# 02-USER_IO_STATUS.net
KiCad netlist of a schematic drawn in Altium Designer
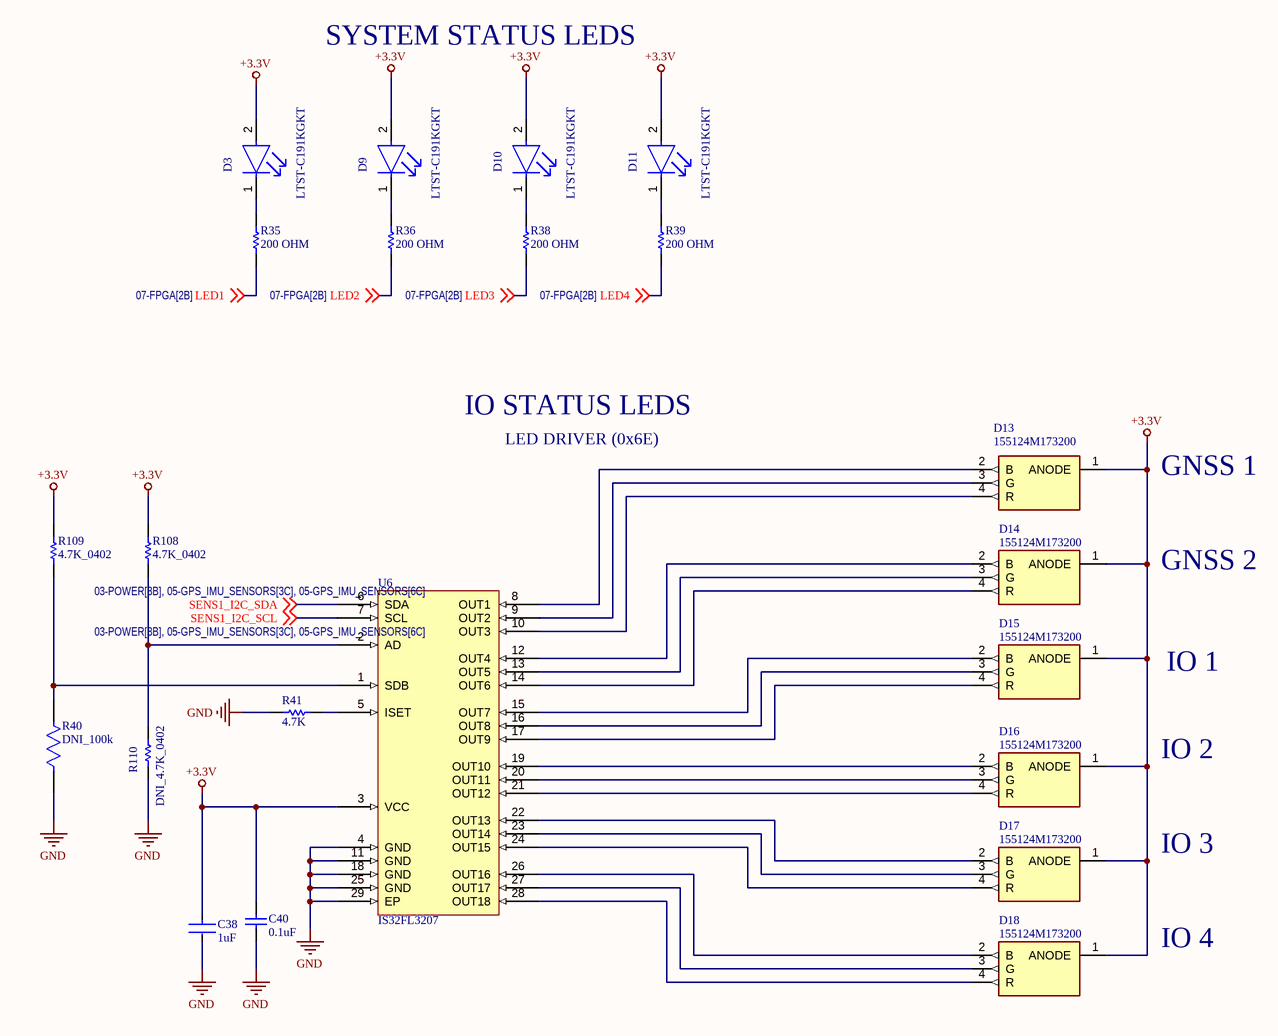
[diagram p0: 02-USER_IO_STATUS.SchDoc]

(export (version "E")
  (design (tool "Eeschema 10.0.6"))
  (components
    (comp (ref "C38")
      (value "1uF")
      (footprint "FP-C0603C105K3PACTU-MFG")
      (description "CAP CER 1UF 25V X5R 0603")
      (fields (field (name "VOLTAGE") "25V") (field (name "TOLERANCE") "10%"))
      (libsource (lib "Altium Content Vault") (part "e9c51b7dd13d4faca003ae77663ab08"))
    )
    (comp (ref "C40")
      (value "0.1uF")
      (footprint "CAPC1608X87X45ML20T05")
      (description "C0603X104K5RACAUTO")
      (fields (field (name "MANUFACTURER") "Kemet"))
      (libsource (lib "Altium Content Vault") (part "CAP"))
    )
    (comp (ref "D3")
      (value "LTST-C191KGKT")
      (footprint "FP-LTST-C191KGKT-MFG")
      (description "LED GREEN CLEAR SMD")
      (libsource (lib "Altium Content Vault") (part "8706943c75ba83719d021d2fdc84c58"))
    )
    (comp (ref "D9")
      (value "LTST-C191KGKT")
      (footprint "FP-LTST-C191KGKT-MFG")
      (description "LED GREEN CLEAR SMD")
      (libsource (lib "Altium Content Vault") (part "8706943c75ba83719d021d2fdc84c58"))
    )
    (comp (ref "D10")
      (value "LTST-C191KGKT")
      (footprint "FP-LTST-C191KGKT-MFG")
      (description "LED GREEN CLEAR SMD")
      (libsource (lib "Altium Content Vault") (part "8706943c75ba83719d021d2fdc84c58"))
    )
    (comp (ref "D11")
      (value "LTST-C191KGKT")
      (footprint "FP-LTST-C191KGKT-MFG")
      (description "LED GREEN CLEAR SMD")
      (libsource (lib "Altium Content Vault") (part "8706943c75ba83719d021d2fdc84c58"))
    )
    (comp (ref "D13")
      (value "155124M173200")
      (footprint "SamacSys:155124M173200")
      (description "LED (Multiple)")
      (fields (field (name "MOUSER PART NUMBER") "710-155124M173200"))
      (libsource (lib "SamacSys") (part "155124M173200"))
    )
    (comp (ref "D14")
      (value "155124M173200")
      (footprint "SamacSys:155124M173200")
      (description "LED (Multiple)")
      (fields (field (name "MOUSER PART NUMBER") "710-155124M173200"))
      (libsource (lib "SamacSys") (part "155124M173200"))
    )
    (comp (ref "D15")
      (value "155124M173200")
      (footprint "SamacSys:155124M173200")
      (description "LED (Multiple)")
      (fields (field (name "MOUSER PART NUMBER") "710-155124M173200"))
      (libsource (lib "SamacSys") (part "155124M173200"))
    )
    (comp (ref "D16")
      (value "155124M173200")
      (footprint "SamacSys:155124M173200")
      (description "LED (Multiple)")
      (fields (field (name "MOUSER PART NUMBER") "710-155124M173200"))
      (libsource (lib "SamacSys") (part "155124M173200"))
    )
    (comp (ref "D17")
      (value "155124M173200")
      (footprint "SamacSys:155124M173200")
      (description "LED (Multiple)")
      (fields (field (name "MOUSER PART NUMBER") "710-155124M173200"))
      (libsource (lib "SamacSys") (part "155124M173200"))
    )
    (comp (ref "D18")
      (value "155124M173200")
      (footprint "SamacSys:155124M173200")
      (description "LED (Multiple)")
      (fields (field (name "MOUSER PART NUMBER") "710-155124M173200"))
      (libsource (lib "SamacSys") (part "155124M173200"))
    )
    (comp (ref "R35")
      (value "200 OHM")
      (footprint "RESC1608X55X30NL15T15")
      (description "ERJ-3EKF2000V")
      (fields (field (name "MANUFACTURER") "Panasonic"))
      (libsource (lib "Altium Content Vault") (part "RES"))
    )
    (comp (ref "R36")
      (value "200 OHM")
      (footprint "RESC1608X55X30NL15T15")
      (description "ERJ-3EKF2000V")
      (fields (field (name "MANUFACTURER") "Panasonic"))
      (libsource (lib "Altium Content Vault") (part "RES"))
    )
    (comp (ref "R38")
      (value "200 OHM")
      (footprint "RESC1608X55X30NL15T15")
      (description "ERJ-3EKF2000V")
      (fields (field (name "MANUFACTURER") "Panasonic"))
      (libsource (lib "Altium Content Vault") (part "RES"))
    )
    (comp (ref "R39")
      (value "200 OHM")
      (footprint "RESC1608X55X30NL15T15")
      (description "ERJ-3EKF2000V")
      (fields (field (name "MANUFACTURER") "Panasonic"))
      (libsource (lib "Altium Content Vault") (part "RES"))
    )
    (comp (ref "R40")
      (value "DNI_100k")
      (footprint "FP-RC0603-0_55-MFG")
      (description "RES SMD 100K OHM 1% 1/10W 0603")
      (fields (field (name "TOLERANCE") "1%"))
      (libsource (lib "Altium Content Vault") (part "1029c3af85768c4190bb7ad29bc67b5"))
    )
    (comp (ref "R41")
      (value "4.7K")
      (footprint "RESC1608X55X30NL15T15")
      (fields (field (name "TOLERANCE") "5%"))
      (libsource (lib "Altium Content Vault") (part "RES-2"))
    )
    (comp (ref "R108")
      (value "4.7K_0402")
      (footprint "RESC1005X40X25LL05T05")
      (description "Chip Resistor, 4.7 KOhm, +/- 1%, 0.1 W, -55 to 155 degC, 0402 (1005 Metric), RoHS, Tape and Reel")
      (fields (field (name "TOLERANCE") "1%") (field (name "PARTNUMBER") "ERJ-2RKF4701X"))
      (libsource (lib "Altium Content Vault") (part "RES-2"))
    )
    (comp (ref "R109")
      (value "4.7K_0402")
      (footprint "RESC1005X40X25LL05T05")
      (description "Chip Resistor, 4.7 KOhm, +/- 1%, 0.1 W, -55 to 155 degC, 0402 (1005 Metric), RoHS, Tape and Reel")
      (fields (field (name "TOLERANCE") "1%") (field (name "PARTNUMBER") "ERJ-2RKF4701X"))
      (libsource (lib "Altium Content Vault") (part "RES-2"))
    )
    (comp (ref "R110")
      (value "DNI_4.7K_0402")
      (footprint "RESC1005X40X25LL05T05")
      (description "Chip Resistor, 4.7 KOhm, +/- 1%, 0.1 W, -55 to 155 degC, 0402 (1005 Metric), RoHS, Tape and Reel")
      (fields (field (name "TOLERANCE") "1%") (field (name "PARTNUMBER") "ERJ-2RKF4701X"))
      (libsource (lib "Altium Content Vault") (part "RES-2"))
    )
    (comp (ref "U6")
      (value "IS32FL3207")
      (footprint "IS32FL3207")
      (libsource (lib "IS32FL3207") (part "IS32FL3207"))
    )
  )
  (nets
    (net (code "1") (name "+3.3V") (class "Default")
      (node (ref "C38") (pin "1") (pinfunction "1_1") (pintype "passive"))
      (node (ref "C40") (pin "2") (pinfunction "2_2") (pintype "passive"))
      (node (ref "D10") (pin "2") (pinfunction "A_2") (pintype "passive"))
      (node (ref "D11") (pin "2") (pinfunction "A_2") (pintype "passive"))
      (node (ref "D13") (pin "1") (pinfunction "ANODE_1") (pintype "power_in"))
      (node (ref "D14") (pin "1") (pinfunction "ANODE_1") (pintype "power_in"))
      (node (ref "D15") (pin "1") (pinfunction "ANODE_1") (pintype "power_in"))
      (node (ref "D16") (pin "1") (pinfunction "ANODE_1") (pintype "power_in"))
      (node (ref "D17") (pin "1") (pinfunction "ANODE_1") (pintype "power_in"))
      (node (ref "D18") (pin "1") (pinfunction "ANODE_1") (pintype "power_in"))
      (node (ref "D3") (pin "2") (pinfunction "A_2") (pintype "passive"))
      (node (ref "D9") (pin "2") (pinfunction "A_2") (pintype "passive"))
      (node (ref "R108") (pin "1") (pinfunction "1_1") (pintype "passive"))
      (node (ref "R109") (pin "1") (pinfunction "1_1") (pintype "passive"))
      (node (ref "U6") (pin "3") (pinfunction "VCC_3") (pintype "input"))
    )
    (net (code "2") (name "GND") (class "Default")
      (node (ref "C38") (pin "2") (pinfunction "2_2") (pintype "passive"))
      (node (ref "C40") (pin "1") (pinfunction "1_1") (pintype "passive"))
      (node (ref "R110") (pin "2") (pinfunction "2_2") (pintype "passive"))
      (node (ref "R40") (pin "1") (pinfunction "1_1") (pintype "passive"))
      (node (ref "R41") (pin "1") (pinfunction "1_1") (pintype "passive"))
      (node (ref "U6") (pin "11") (pinfunction "GND_11") (pintype "input"))
      (node (ref "U6") (pin "18") (pinfunction "GND_18") (pintype "input"))
      (node (ref "U6") (pin "25") (pinfunction "GND_25") (pintype "input"))
      (node (ref "U6") (pin "29") (pinfunction "EP_29") (pintype "input"))
      (node (ref "U6") (pin "4") (pinfunction "GND_4") (pintype "input"))
    )
    (net (code "3") (name "LED1") (class "Default")
      (node (ref "R35") (pin "1") (pinfunction "1_1") (pintype "passive"))
    )
    (net (code "4") (name "LED2") (class "Default")
      (node (ref "R36") (pin "1") (pinfunction "1_1") (pintype "passive"))
    )
    (net (code "5") (name "LED3") (class "Default")
      (node (ref "R38") (pin "1") (pinfunction "1_1") (pintype "passive"))
    )
    (net (code "6") (name "LED4") (class "Default")
      (node (ref "R39") (pin "1") (pinfunction "1_1") (pintype "passive"))
    )
    (net (code "7") (name "Net-(D3-C)") (class "Default")
      (node (ref "D3") (pin "1") (pinfunction "C_1") (pintype "passive"))
      (node (ref "R35") (pin "2") (pinfunction "2_2") (pintype "passive"))
    )
    (net (code "8") (name "Net-(D9-C)") (class "Default")
      (node (ref "D9") (pin "1") (pinfunction "C_1") (pintype "passive"))
      (node (ref "R36") (pin "2") (pinfunction "2_2") (pintype "passive"))
    )
    (net (code "9") (name "Net-(D10-C)") (class "Default")
      (node (ref "D10") (pin "1") (pinfunction "C_1") (pintype "passive"))
      (node (ref "R38") (pin "2") (pinfunction "2_2") (pintype "passive"))
    )
    (net (code "10") (name "Net-(D11-C)") (class "Default")
      (node (ref "D11") (pin "1") (pinfunction "C_1") (pintype "passive"))
      (node (ref "R39") (pin "2") (pinfunction "2_2") (pintype "passive"))
    )
    (net (code "11") (name "Net-(D13-B)") (class "Default")
      (node (ref "D13") (pin "2") (pinfunction "B_2") (pintype "output"))
      (node (ref "U6") (pin "8") (pinfunction "OUT1_8") (pintype "input"))
    )
    (net (code "12") (name "Net-(D13-G)") (class "Default")
      (node (ref "D13") (pin "3") (pinfunction "G_3") (pintype "output"))
      (node (ref "U6") (pin "9") (pinfunction "OUT2_9") (pintype "input"))
    )
    (net (code "13") (name "Net-(D13-R)") (class "Default")
      (node (ref "D13") (pin "4") (pinfunction "R_4") (pintype "output"))
      (node (ref "U6") (pin "10") (pinfunction "OUT3_10") (pintype "input"))
    )
    (net (code "14") (name "Net-(D14-B)") (class "Default")
      (node (ref "D14") (pin "2") (pinfunction "B_2") (pintype "output"))
      (node (ref "U6") (pin "12") (pinfunction "OUT4_12") (pintype "input"))
    )
    (net (code "15") (name "Net-(D14-G)") (class "Default")
      (node (ref "D14") (pin "3") (pinfunction "G_3") (pintype "output"))
      (node (ref "U6") (pin "13") (pinfunction "OUT5_13") (pintype "input"))
    )
    (net (code "16") (name "Net-(D14-R)") (class "Default")
      (node (ref "D14") (pin "4") (pinfunction "R_4") (pintype "output"))
      (node (ref "U6") (pin "14") (pinfunction "OUT6_14") (pintype "input"))
    )
    (net (code "17") (name "Net-(D15-B)") (class "Default")
      (node (ref "D15") (pin "2") (pinfunction "B_2") (pintype "output"))
      (node (ref "U6") (pin "15") (pinfunction "OUT7_15") (pintype "input"))
    )
    (net (code "18") (name "Net-(D15-G)") (class "Default")
      (node (ref "D15") (pin "3") (pinfunction "G_3") (pintype "output"))
      (node (ref "U6") (pin "16") (pinfunction "OUT8_16") (pintype "input"))
    )
    (net (code "19") (name "Net-(D15-R)") (class "Default")
      (node (ref "D15") (pin "4") (pinfunction "R_4") (pintype "output"))
      (node (ref "U6") (pin "17") (pinfunction "OUT9_17") (pintype "input"))
    )
    (net (code "20") (name "Net-(D16-B)") (class "Default")
      (node (ref "D16") (pin "2") (pinfunction "B_2") (pintype "output"))
      (node (ref "U6") (pin "19") (pinfunction "OUT10_19") (pintype "input"))
    )
    (net (code "21") (name "Net-(D16-G)") (class "Default")
      (node (ref "D16") (pin "3") (pinfunction "G_3") (pintype "output"))
      (node (ref "U6") (pin "20") (pinfunction "OUT11_20") (pintype "input"))
    )
    (net (code "22") (name "Net-(D16-R)") (class "Default")
      (node (ref "D16") (pin "4") (pinfunction "R_4") (pintype "output"))
      (node (ref "U6") (pin "21") (pinfunction "OUT12_21") (pintype "input"))
    )
    (net (code "23") (name "Net-(D17-B)") (class "Default")
      (node (ref "D17") (pin "2") (pinfunction "B_2") (pintype "output"))
      (node (ref "U6") (pin "22") (pinfunction "OUT13_22") (pintype "input"))
    )
    (net (code "24") (name "Net-(D17-G)") (class "Default")
      (node (ref "D17") (pin "3") (pinfunction "G_3") (pintype "output"))
      (node (ref "U6") (pin "23") (pinfunction "OUT14_23") (pintype "input"))
    )
    (net (code "25") (name "Net-(D17-R)") (class "Default")
      (node (ref "D17") (pin "4") (pinfunction "R_4") (pintype "output"))
      (node (ref "U6") (pin "24") (pinfunction "OUT15_24") (pintype "input"))
    )
    (net (code "26") (name "Net-(D18-B)") (class "Default")
      (node (ref "D18") (pin "2") (pinfunction "B_2") (pintype "output"))
      (node (ref "U6") (pin "26") (pinfunction "OUT16_26") (pintype "input"))
    )
    (net (code "27") (name "Net-(D18-G)") (class "Default")
      (node (ref "D18") (pin "3") (pinfunction "G_3") (pintype "output"))
      (node (ref "U6") (pin "27") (pinfunction "OUT17_27") (pintype "input"))
    )
    (net (code "28") (name "Net-(D18-R)") (class "Default")
      (node (ref "D18") (pin "4") (pinfunction "R_4") (pintype "output"))
      (node (ref "U6") (pin "28") (pinfunction "OUT18_28") (pintype "input"))
    )
    (net (code "29") (name "Net-(U6-AD)") (class "Default")
      (node (ref "R108") (pin "2") (pinfunction "2_2") (pintype "passive"))
      (node (ref "R110") (pin "1") (pinfunction "1_1") (pintype "passive"))
      (node (ref "U6") (pin "2") (pinfunction "AD_2") (pintype "input"))
    )
    (net (code "30") (name "Net-(U6-ISET)") (class "Default")
      (node (ref "R41") (pin "2") (pinfunction "2_2") (pintype "passive"))
      (node (ref "U6") (pin "5") (pinfunction "ISET_5") (pintype "input"))
    )
    (net (code "31") (name "Net-(U6-SDB)") (class "Default")
      (node (ref "R109") (pin "2") (pinfunction "2_2") (pintype "passive"))
      (node (ref "R40") (pin "2") (pinfunction "2_2") (pintype "passive"))
      (node (ref "U6") (pin "1") (pinfunction "SDB_1") (pintype "input"))
    )
    (net (code "32") (name "SENS1_I2C_SCL") (class "Default")
      (node (ref "U6") (pin "7") (pinfunction "SCL_7") (pintype "input"))
    )
    (net (code "33") (name "SENS1_I2C_SDA") (class "Default")
      (node (ref "U6") (pin "6") (pinfunction "SDA_6") (pintype "input"))
    )
  )
)
